# qfn-20-4mm-0_5mm-socket-pcb-mk-1_0_0.net
KiCad netlist of a schematic drawn in EAGLE
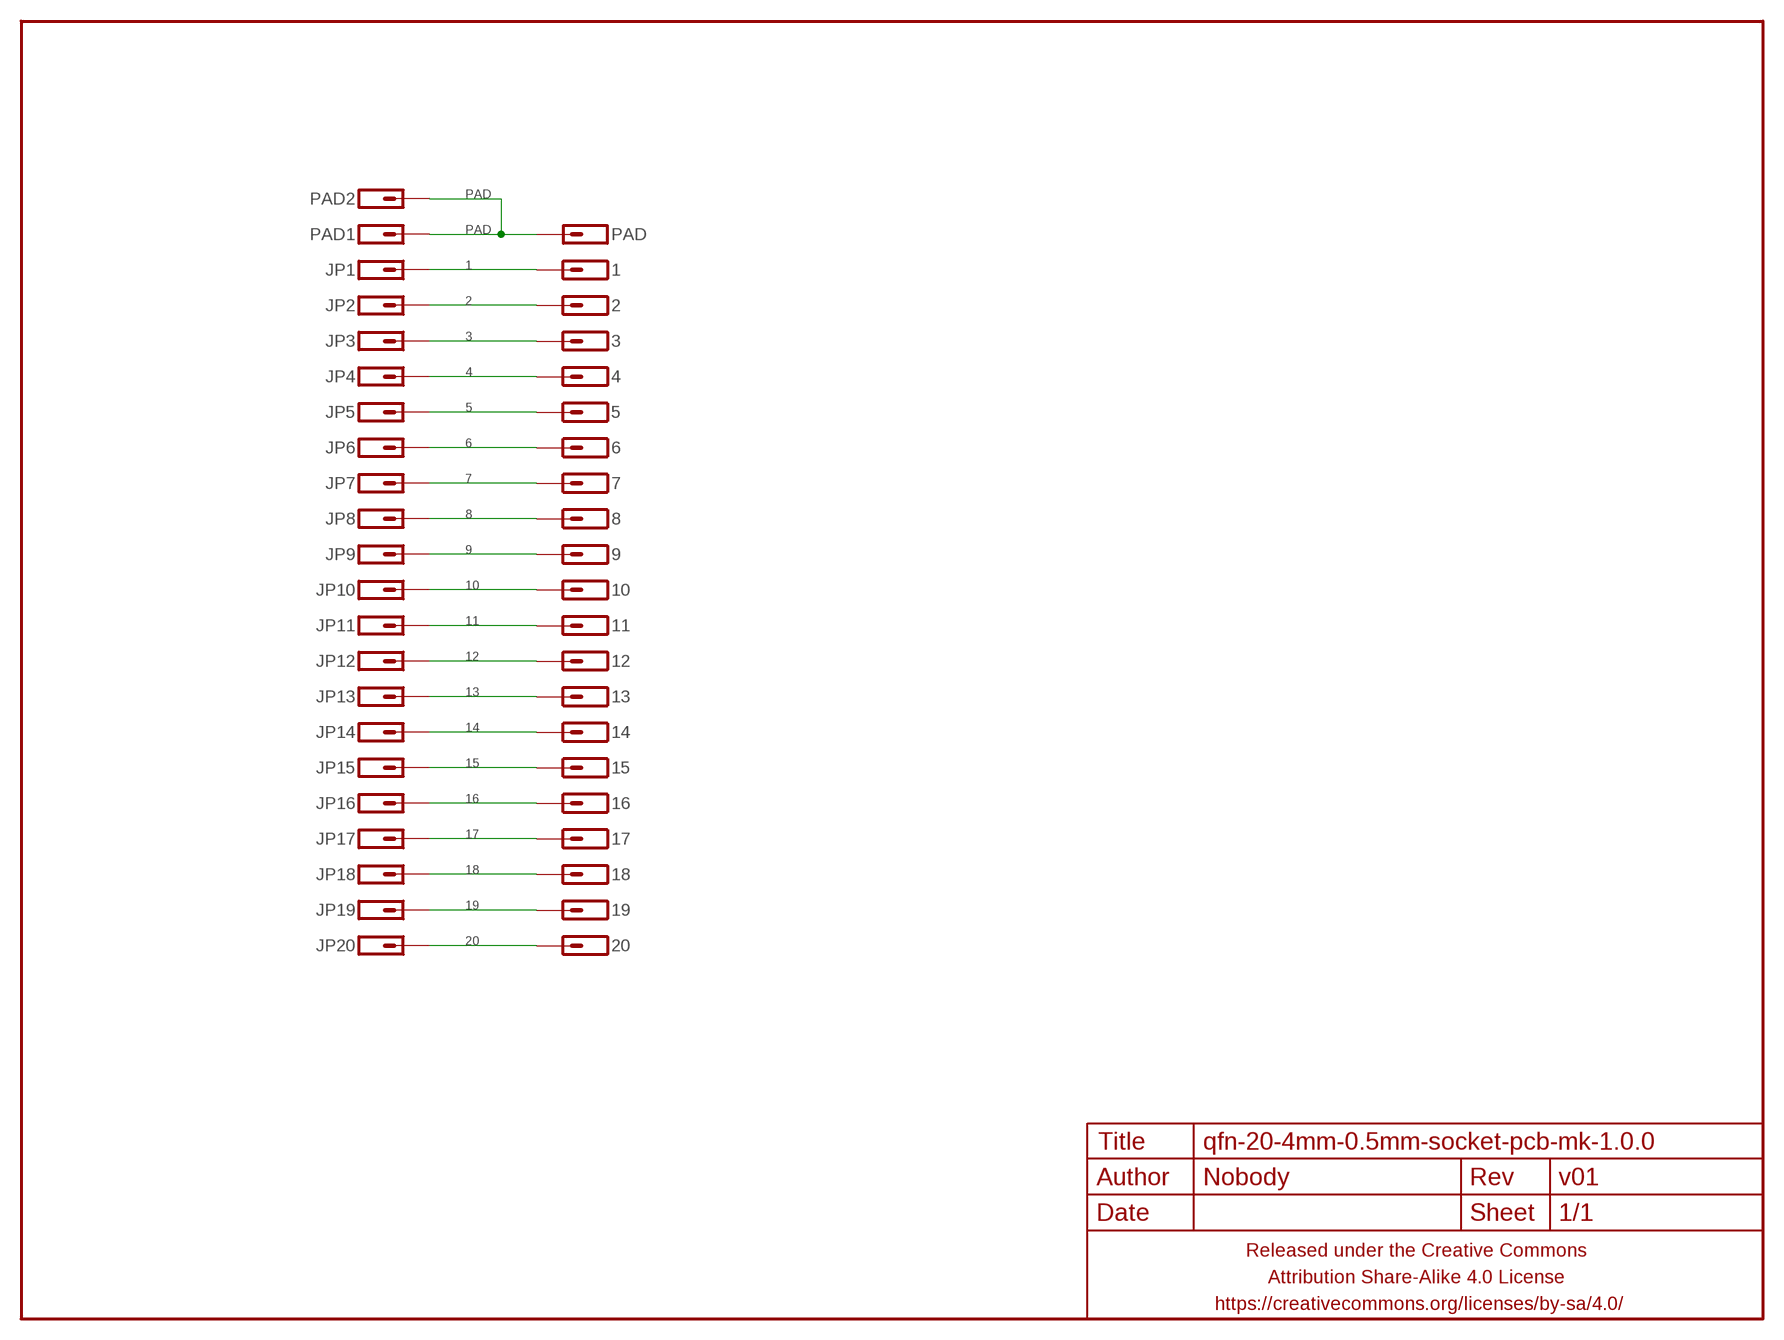
[diagram p0: schematic, sheet 1]

(export (version "E")
  (design (tool "Eeschema 10.0.6"))
  (components
    (comp (ref "1")
      (value "M01PTH")
      (footprint "eagle-import:1X01")
      (libsource (lib "eagle-import") (part "M01PTH"))
    )
    (comp (ref "2")
      (value "M01PTH")
      (footprint "eagle-import:1X01")
      (libsource (lib "eagle-import") (part "M01PTH"))
    )
    (comp (ref "3")
      (value "M01PTH")
      (footprint "eagle-import:1X01")
      (libsource (lib "eagle-import") (part "M01PTH"))
    )
    (comp (ref "4")
      (value "M01PTH")
      (footprint "eagle-import:1X01")
      (libsource (lib "eagle-import") (part "M01PTH"))
    )
    (comp (ref "5")
      (value "M01PTH")
      (footprint "eagle-import:1X01")
      (libsource (lib "eagle-import") (part "M01PTH"))
    )
    (comp (ref "6")
      (value "M01PTH")
      (footprint "eagle-import:1X01")
      (libsource (lib "eagle-import") (part "M01PTH"))
    )
    (comp (ref "7")
      (value "M01PTH")
      (footprint "eagle-import:1X01")
      (libsource (lib "eagle-import") (part "M01PTH"))
    )
    (comp (ref "8")
      (value "M01PTH")
      (footprint "eagle-import:1X01")
      (libsource (lib "eagle-import") (part "M01PTH"))
    )
    (comp (ref "9")
      (value "M01PTH")
      (footprint "eagle-import:1X01")
      (libsource (lib "eagle-import") (part "M01PTH"))
    )
    (comp (ref "10")
      (value "M01PTH")
      (footprint "eagle-import:1X01")
      (libsource (lib "eagle-import") (part "M01PTH"))
    )
    (comp (ref "11")
      (value "M01PTH")
      (footprint "eagle-import:1X01")
      (libsource (lib "eagle-import") (part "M01PTH"))
    )
    (comp (ref "12")
      (value "M01PTH")
      (footprint "eagle-import:1X01")
      (libsource (lib "eagle-import") (part "M01PTH"))
    )
    (comp (ref "13")
      (value "M01PTH")
      (footprint "eagle-import:1X01")
      (libsource (lib "eagle-import") (part "M01PTH"))
    )
    (comp (ref "14")
      (value "M01PTH")
      (footprint "eagle-import:1X01")
      (libsource (lib "eagle-import") (part "M01PTH"))
    )
    (comp (ref "15")
      (value "M01PTH")
      (footprint "eagle-import:1X01")
      (libsource (lib "eagle-import") (part "M01PTH"))
    )
    (comp (ref "16")
      (value "M01PTH")
      (footprint "eagle-import:1X01")
      (libsource (lib "eagle-import") (part "M01PTH"))
    )
    (comp (ref "17")
      (value "M01PTH")
      (footprint "eagle-import:1X01")
      (libsource (lib "eagle-import") (part "M01PTH"))
    )
    (comp (ref "18")
      (value "M01PTH")
      (footprint "eagle-import:1X01")
      (libsource (lib "eagle-import") (part "M01PTH"))
    )
    (comp (ref "19")
      (value "M01PTH")
      (footprint "eagle-import:1X01")
      (libsource (lib "eagle-import") (part "M01PTH"))
    )
    (comp (ref "20")
      (value "M01PTH")
      (footprint "eagle-import:1X01")
      (libsource (lib "eagle-import") (part "M01PTH"))
    )
    (comp (ref "FRAME1")
      (value "FRAME-LETTERNO_PACKAGE")
      (footprint "eagle-import:DUMMY")
      (fields (field (name "DESIGNER") "Nobody") (field (name "VERSION") "v01"))
      (libsource (lib "eagle-import") (part "FRAME-LETTERNO_PACKAGE"))
    )
    (comp (ref "JP1")
      (value "M01PTH-0.4MM")
      (footprint "eagle-import:1X01-0.4MM")
      (libsource (lib "eagle-import") (part "M01PTH-0.4MM"))
    )
    (comp (ref "JP2")
      (value "M01PTH-0.4MM")
      (footprint "eagle-import:1X01-0.4MM")
      (libsource (lib "eagle-import") (part "M01PTH-0.4MM"))
    )
    (comp (ref "JP3")
      (value "M01PTH-0.4MM")
      (footprint "eagle-import:1X01-0.4MM")
      (libsource (lib "eagle-import") (part "M01PTH-0.4MM"))
    )
    (comp (ref "JP4")
      (value "M01PTH-0.4MM")
      (footprint "eagle-import:1X01-0.4MM")
      (libsource (lib "eagle-import") (part "M01PTH-0.4MM"))
    )
    (comp (ref "JP5")
      (value "M01PTH-0.4MM")
      (footprint "eagle-import:1X01-0.4MM")
      (libsource (lib "eagle-import") (part "M01PTH-0.4MM"))
    )
    (comp (ref "JP6")
      (value "M01PTH-0.4MM")
      (footprint "eagle-import:1X01-0.4MM")
      (libsource (lib "eagle-import") (part "M01PTH-0.4MM"))
    )
    (comp (ref "JP7")
      (value "M01PTH-0.4MM")
      (footprint "eagle-import:1X01-0.4MM")
      (libsource (lib "eagle-import") (part "M01PTH-0.4MM"))
    )
    (comp (ref "JP8")
      (value "M01PTH-0.4MM")
      (footprint "eagle-import:1X01-0.4MM")
      (libsource (lib "eagle-import") (part "M01PTH-0.4MM"))
    )
    (comp (ref "JP9")
      (value "M01PTH-0.4MM")
      (footprint "eagle-import:1X01-0.4MM")
      (libsource (lib "eagle-import") (part "M01PTH-0.4MM"))
    )
    (comp (ref "JP10")
      (value "M01PTH-0.4MM")
      (footprint "eagle-import:1X01-0.4MM")
      (libsource (lib "eagle-import") (part "M01PTH-0.4MM"))
    )
    (comp (ref "JP11")
      (value "M01PTH-0.4MM")
      (footprint "eagle-import:1X01-0.4MM")
      (libsource (lib "eagle-import") (part "M01PTH-0.4MM"))
    )
    (comp (ref "JP12")
      (value "M01PTH-0.4MM")
      (footprint "eagle-import:1X01-0.4MM")
      (libsource (lib "eagle-import") (part "M01PTH-0.4MM"))
    )
    (comp (ref "JP13")
      (value "M01PTH-0.4MM")
      (footprint "eagle-import:1X01-0.4MM")
      (libsource (lib "eagle-import") (part "M01PTH-0.4MM"))
    )
    (comp (ref "JP14")
      (value "M01PTH-0.4MM")
      (footprint "eagle-import:1X01-0.4MM")
      (libsource (lib "eagle-import") (part "M01PTH-0.4MM"))
    )
    (comp (ref "JP15")
      (value "M01PTH-0.4MM")
      (footprint "eagle-import:1X01-0.4MM")
      (libsource (lib "eagle-import") (part "M01PTH-0.4MM"))
    )
    (comp (ref "JP16")
      (value "M01PTH-0.4MM")
      (footprint "eagle-import:1X01-0.4MM")
      (libsource (lib "eagle-import") (part "M01PTH-0.4MM"))
    )
    (comp (ref "JP17")
      (value "M01PTH-0.4MM")
      (footprint "eagle-import:1X01-0.4MM")
      (libsource (lib "eagle-import") (part "M01PTH-0.4MM"))
    )
    (comp (ref "JP18")
      (value "M01PTH-0.4MM")
      (footprint "eagle-import:1X01-0.4MM")
      (libsource (lib "eagle-import") (part "M01PTH-0.4MM"))
    )
    (comp (ref "JP19")
      (value "M01PTH-0.4MM")
      (footprint "eagle-import:1X01-0.4MM")
      (libsource (lib "eagle-import") (part "M01PTH-0.4MM"))
    )
    (comp (ref "JP20")
      (value "M01PTH-0.4MM")
      (footprint "eagle-import:1X01-0.4MM")
      (libsource (lib "eagle-import") (part "M01PTH-0.4MM"))
    )
    (comp (ref "PAD")
      (value "M01PTH-1MM-CIR-NS")
      (footprint "eagle-import:1X01-1MM-CIR-NS")
      (libsource (lib "eagle-import") (part "M01PTH-1MM-CIR-NS"))
    )
    (comp (ref "PAD1")
      (value "M01PTH")
      (footprint "eagle-import:1X01")
      (libsource (lib "eagle-import") (part "M01PTH"))
    )
    (comp (ref "PAD2")
      (value "M01PTH")
      (footprint "eagle-import:1X01")
      (libsource (lib "eagle-import") (part "M01PTH"))
    )
  )
  (nets
    (net (code "1") (name "/1") (class "Default")
      (node (ref "1") (pin "1") (pinfunction "1_1") (pintype "passive"))
      (node (ref "JP1") (pin "P$1") (pinfunction "1_P$1") (pintype "passive"))
    )
    (net (code "2") (name "/2") (class "Default")
      (node (ref "2") (pin "1") (pinfunction "1_1") (pintype "passive"))
      (node (ref "JP2") (pin "P$1") (pinfunction "1_P$1") (pintype "passive"))
    )
    (net (code "3") (name "/3") (class "Default")
      (node (ref "3") (pin "1") (pinfunction "1_1") (pintype "passive"))
      (node (ref "JP3") (pin "P$1") (pinfunction "1_P$1") (pintype "passive"))
    )
    (net (code "4") (name "/4") (class "Default")
      (node (ref "4") (pin "1") (pinfunction "1_1") (pintype "passive"))
      (node (ref "JP4") (pin "P$1") (pinfunction "1_P$1") (pintype "passive"))
    )
    (net (code "5") (name "/5") (class "Default")
      (node (ref "5") (pin "1") (pinfunction "1_1") (pintype "passive"))
      (node (ref "JP5") (pin "P$1") (pinfunction "1_P$1") (pintype "passive"))
    )
    (net (code "6") (name "/6") (class "Default")
      (node (ref "6") (pin "1") (pinfunction "1_1") (pintype "passive"))
      (node (ref "JP6") (pin "P$1") (pinfunction "1_P$1") (pintype "passive"))
    )
    (net (code "7") (name "/7") (class "Default")
      (node (ref "7") (pin "1") (pinfunction "1_1") (pintype "passive"))
      (node (ref "JP7") (pin "P$1") (pinfunction "1_P$1") (pintype "passive"))
    )
    (net (code "8") (name "/8") (class "Default")
      (node (ref "8") (pin "1") (pinfunction "1_1") (pintype "passive"))
      (node (ref "JP8") (pin "P$1") (pinfunction "1_P$1") (pintype "passive"))
    )
    (net (code "9") (name "/9") (class "Default")
      (node (ref "9") (pin "1") (pinfunction "1_1") (pintype "passive"))
      (node (ref "JP9") (pin "P$1") (pinfunction "1_P$1") (pintype "passive"))
    )
    (net (code "10") (name "/10") (class "Default")
      (node (ref "10") (pin "1") (pinfunction "1_1") (pintype "passive"))
      (node (ref "JP10") (pin "P$1") (pinfunction "1_P$1") (pintype "passive"))
    )
    (net (code "11") (name "/11") (class "Default")
      (node (ref "11") (pin "1") (pinfunction "1_1") (pintype "passive"))
      (node (ref "JP11") (pin "P$1") (pinfunction "1_P$1") (pintype "passive"))
    )
    (net (code "12") (name "/12") (class "Default")
      (node (ref "12") (pin "1") (pinfunction "1_1") (pintype "passive"))
      (node (ref "JP12") (pin "P$1") (pinfunction "1_P$1") (pintype "passive"))
    )
    (net (code "13") (name "/13") (class "Default")
      (node (ref "13") (pin "1") (pinfunction "1_1") (pintype "passive"))
      (node (ref "JP13") (pin "P$1") (pinfunction "1_P$1") (pintype "passive"))
    )
    (net (code "14") (name "/14") (class "Default")
      (node (ref "14") (pin "1") (pinfunction "1_1") (pintype "passive"))
      (node (ref "JP14") (pin "P$1") (pinfunction "1_P$1") (pintype "passive"))
    )
    (net (code "15") (name "/15") (class "Default")
      (node (ref "15") (pin "1") (pinfunction "1_1") (pintype "passive"))
      (node (ref "JP15") (pin "P$1") (pinfunction "1_P$1") (pintype "passive"))
    )
    (net (code "16") (name "/16") (class "Default")
      (node (ref "16") (pin "1") (pinfunction "1_1") (pintype "passive"))
      (node (ref "JP16") (pin "P$1") (pinfunction "1_P$1") (pintype "passive"))
    )
    (net (code "17") (name "/17") (class "Default")
      (node (ref "17") (pin "1") (pinfunction "1_1") (pintype "passive"))
      (node (ref "JP17") (pin "P$1") (pinfunction "1_P$1") (pintype "passive"))
    )
    (net (code "18") (name "/18") (class "Default")
      (node (ref "18") (pin "1") (pinfunction "1_1") (pintype "passive"))
      (node (ref "JP18") (pin "P$1") (pinfunction "1_P$1") (pintype "passive"))
    )
    (net (code "19") (name "/19") (class "Default")
      (node (ref "19") (pin "1") (pinfunction "1_1") (pintype "passive"))
      (node (ref "JP19") (pin "P$1") (pinfunction "1_P$1") (pintype "passive"))
    )
    (net (code "20") (name "/20") (class "Default")
      (node (ref "20") (pin "1") (pinfunction "1_1") (pintype "passive"))
      (node (ref "JP20") (pin "P$1") (pinfunction "1_P$1") (pintype "passive"))
    )
    (net (code "21") (name "/PAD") (class "Default")
      (node (ref "PAD") (pin "1") (pinfunction "1_1") (pintype "passive"))
      (node (ref "PAD1") (pin "1") (pinfunction "1_1") (pintype "passive"))
      (node (ref "PAD2") (pin "1") (pinfunction "1_1") (pintype "passive"))
    )
  )
)
